# transciever_test_schematic.net
KiCad netlist of a schematic drawn in EAGLE
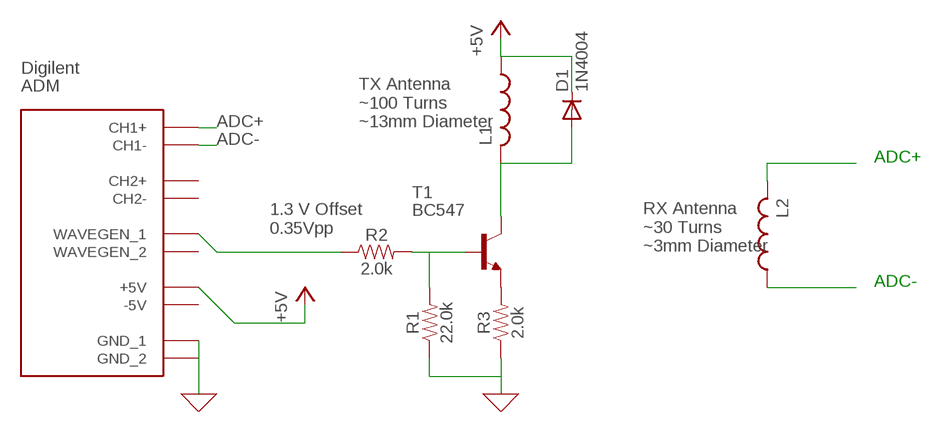
[diagram p0: schematic, sheet 1]

(export (version "E")
  (design (tool "Eeschema 10.0.6"))
  (components
    (comp (ref "D1")
      (value "1N4004")
      (footprint "eagle-import:DO41-10")
      (libsource (lib "eagle-import") (part "1N4004"))
    )
    (comp (ref "L1")
      (value "L-USIR-4")
      (footprint "eagle-import:IR-4")
      (libsource (lib "eagle-import") (part "L-USIR-4"))
    )
    (comp (ref "L2")
      (value "L-USIR-4")
      (footprint "eagle-import:IR-4")
      (libsource (lib "eagle-import") (part "L-USIR-4"))
    )
    (comp (ref "R1")
      (value "22.0k")
      (footprint "eagle-import:0603")
      (libsource (lib "eagle-import") (part "2.0KOHM-0603-1/10W-5%"))
    )
    (comp (ref "R2")
      (value "2.0k")
      (footprint "eagle-import:0603")
      (libsource (lib "eagle-import") (part "2.0KOHM-0603-1/10W-5%"))
    )
    (comp (ref "R3")
      (value "2.0k")
      (footprint "eagle-import:0603")
      (libsource (lib "eagle-import") (part "2.0KOHM-0603-1/10W-5%"))
    )
    (comp (ref "T1")
      (value "BC547")
      (footprint "eagle-import:TO92")
      (libsource (lib "eagle-import") (part "BC547"))
    )
    (comp (ref "U$2")
      (value "DIGILENT_ADM")
      (footprint "eagle-import:DIGILENT_ADM")
      (libsource (lib "eagle-import") (part "DIGILENT_ADM"))
    )
  )
  (nets
    (net (code "1") (name "+5V") (class "Default")
      (node (ref "D1") (pin "C") (pinfunction "C_C") (pintype "passive"))
      (node (ref "L1") (pin "1") (pinfunction "1_1") (pintype "passive"))
      (node (ref "U$2") (pin "+5V") (pinfunction "+5V_+5V") (pintype "bidirectional"))
    )
    (net (code "2") (name "/ADC+") (class "Default")
      (node (ref "U$2") (pin "CH1+") (pinfunction "CH1+_CH1+") (pintype "bidirectional"))
    )
    (net (code "3") (name "/ADC-") (class "Default")
      (node (ref "U$2") (pin "CH1-") (pinfunction "CH1-_CH1-") (pintype "bidirectional"))
    )
    (net (code "4") (name "GND") (class "Default")
      (node (ref "R1") (pin "1") (pinfunction "1_1") (pintype "passive"))
      (node (ref "R3") (pin "1") (pinfunction "1_1") (pintype "passive"))
      (node (ref "U$2") (pin "GND_2") (pinfunction "GND_1_GND_2") (pintype "bidirectional"))
    )
    (net (code "5") (name "Net-(R2-Pad1)") (class "Default")
      (node (ref "R2") (pin "1") (pinfunction "1_1") (pintype "passive"))
      (node (ref "U$2") (pin "WAVEGEN_1") (pinfunction "WAVEGEN_1_WAVEGEN_1") (pintype "bidirectional"))
    )
    (net (code "6") (name "Net-(T1-B)") (class "Default")
      (node (ref "R1") (pin "2") (pinfunction "2_2") (pintype "passive"))
      (node (ref "R2") (pin "2") (pinfunction "2_2") (pintype "passive"))
      (node (ref "T1") (pin "2") (pinfunction "B_2") (pintype "passive"))
    )
    (net (code "7") (name "Net-(T1-C)") (class "Default")
      (node (ref "D1") (pin "A") (pinfunction "A_A") (pintype "passive"))
      (node (ref "L1") (pin "2") (pinfunction "2_2") (pintype "passive"))
      (node (ref "T1") (pin "3") (pinfunction "C_3") (pintype "passive"))
    )
    (net (code "8") (name "Net-(T1-E)") (class "Default")
      (node (ref "R3") (pin "2") (pinfunction "2_2") (pintype "passive"))
      (node (ref "T1") (pin "1") (pinfunction "E_1") (pintype "passive"))
    )
    (net (code "9") (name "unconnected-(L2-Pad1)") (class "Default")
      (node (ref "L2") (pin "1") (pinfunction "1_1") (pintype "passive"))
    )
    (net (code "10") (name "unconnected-(L2-Pad2)") (class "Default")
      (node (ref "L2") (pin "2") (pinfunction "2_2") (pintype "passive"))
    )
    (net (code "11") (name "unconnected-(U$2-GND_2-PadGND)") (class "Default")
      (node (ref "U$2") (pin "GND") (pinfunction "GND_2_GND") (pintype "bidirectional"))
    )
    (net (code "12") (name "unconnected-(U$2-Pad-5V)") (class "Default")
      (node (ref "U$2") (pin "-5V") (pinfunction "-5V_-5V") (pintype "bidirectional"))
    )
    (net (code "13") (name "unconnected-(U$2-PadCH2+)") (class "Default")
      (node (ref "U$2") (pin "CH2+") (pinfunction "CH2+_CH2+") (pintype "bidirectional"))
    )
    (net (code "14") (name "unconnected-(U$2-PadCH2-)") (class "Default")
      (node (ref "U$2") (pin "CH2-") (pinfunction "CH2-_CH2-") (pintype "bidirectional"))
    )
    (net (code "15") (name "unconnected-(U$2-PadWAVEGEN_2)") (class "Default")
      (node (ref "U$2") (pin "WAVEGEN_2") (pinfunction "WAVEGEN_2_WAVEGEN_2") (pintype "bidirectional"))
    )
  )
)
